# cc2652p_rf-star.net
KiCad netlist of a schematic drawn in EAGLE
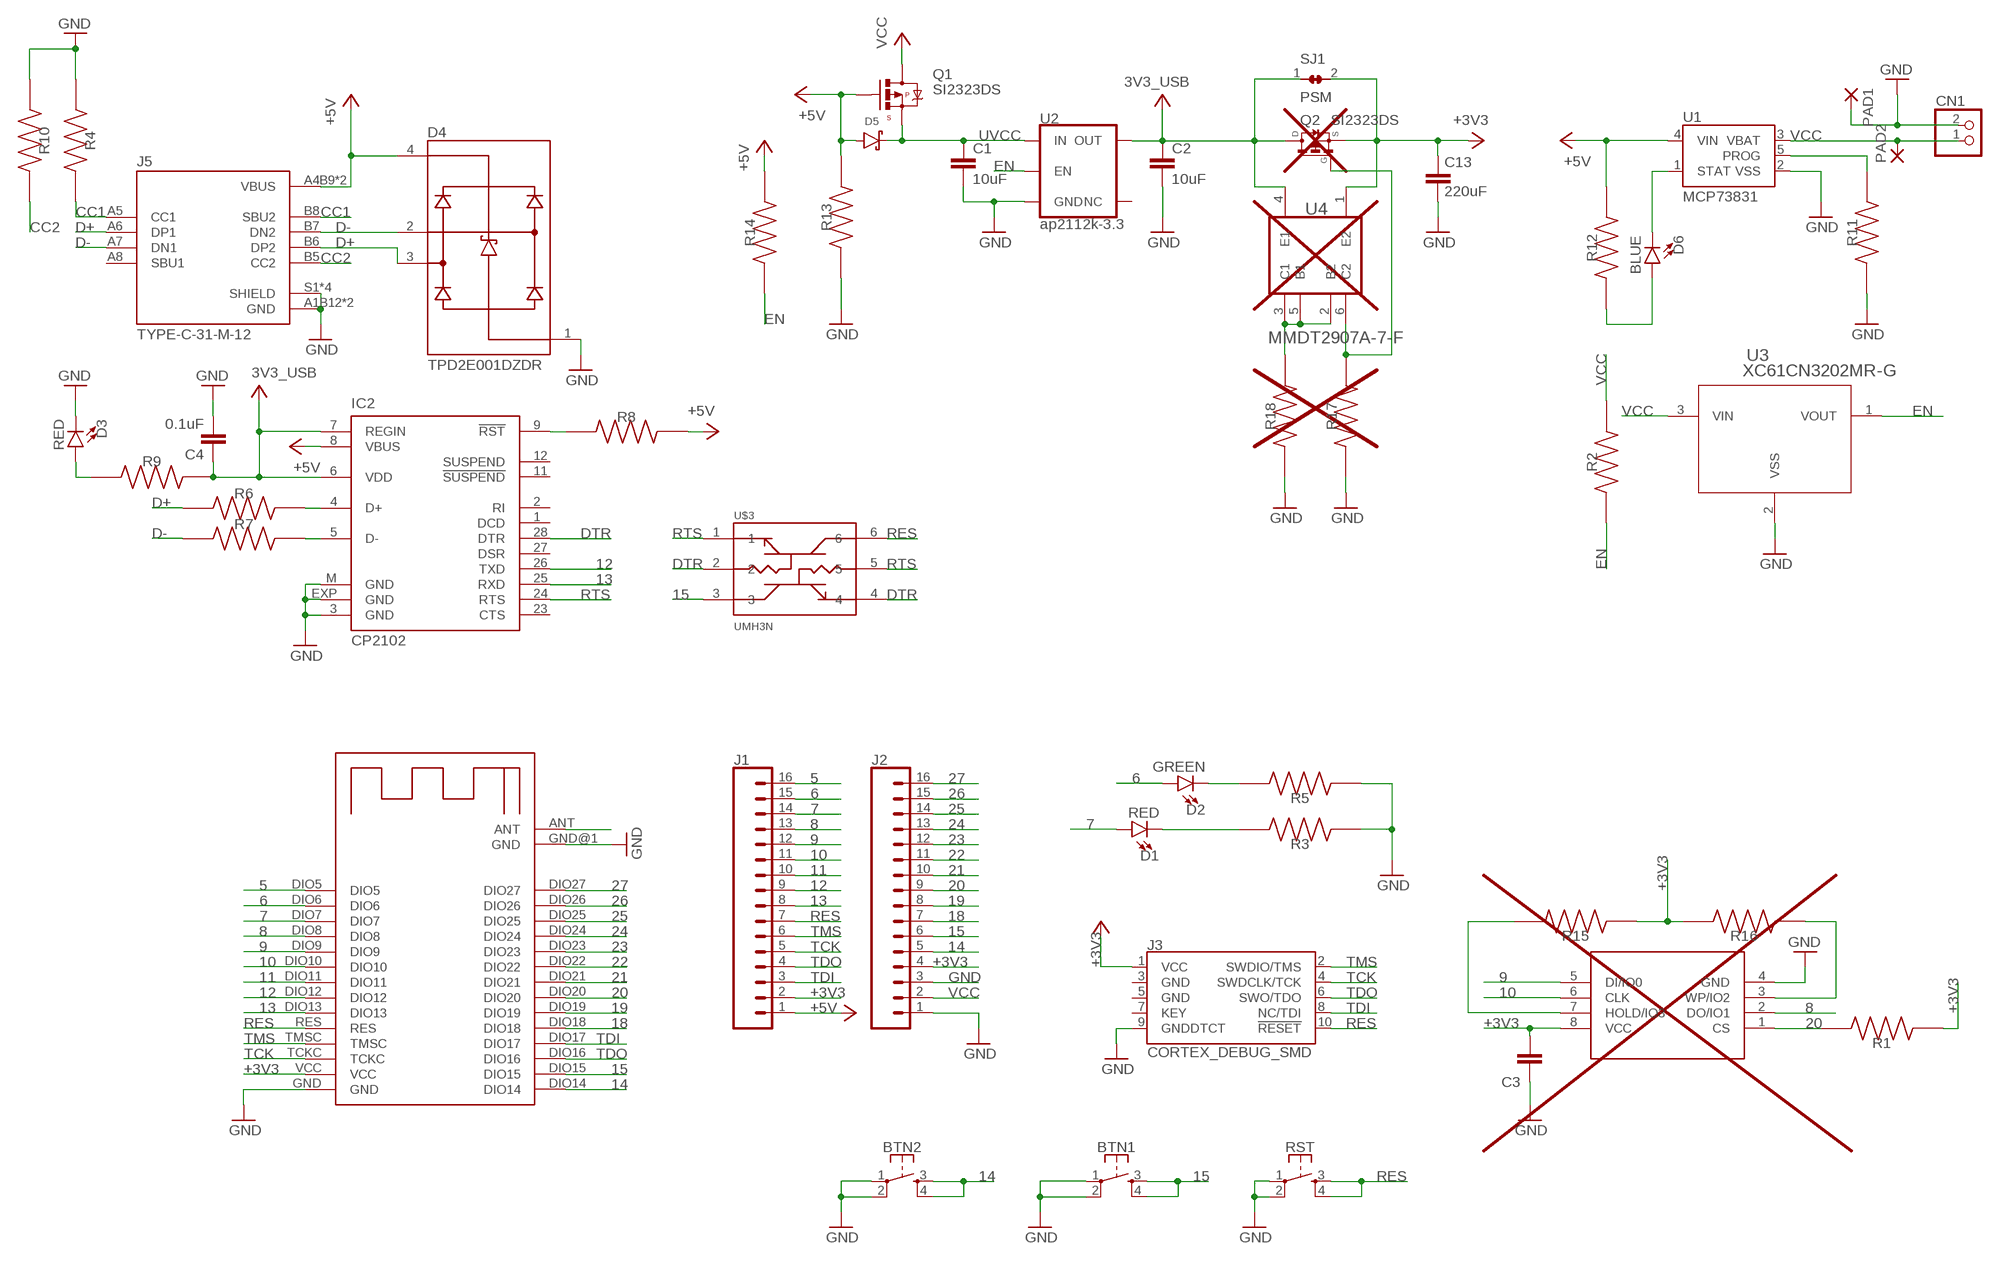
[diagram p0: schematic, sheet 1]

(export (version "E")
  (design (tool "Eeschema 10.0.6"))
  (components
    (comp (ref "BTN1")
      (value "MOMENTARY-SWITCH-SPST-2-SMD-4.6X2.8MM")
      (footprint "eagle-import:TACTILE_SWITCH_SMD_4.6X2.8MM")
      (libsource (lib "eagle-import") (part "MOMENTARY-SWITCH-SPST-2-SMD-4.6X2.8MM"))
    )
    (comp (ref "BTN2")
      (value "MOMENTARY-SWITCH-SPST-2-SMD-4.6X2.8MM")
      (footprint "eagle-import:TACTILE_SWITCH_SMD_4.6X2.8MM")
      (libsource (lib "eagle-import") (part "MOMENTARY-SWITCH-SPST-2-SMD-4.6X2.8MM"))
    )
    (comp (ref "C1")
      (value "10uF")
      (footprint "eagle-import:0603")
      (libsource (lib "eagle-import") (part "10UF-0603-6.3V-20%"))
    )
    (comp (ref "C2")
      (value "10uF")
      (footprint "eagle-import:0603")
      (libsource (lib "eagle-import") (part "10UF-0603-6.3V-20%"))
    )
    (comp (ref "C3")
      (value "100n")
      (footprint "eagle-import:CAPC1005X40N")
      (fields (field (name "MF") "Yageo") (field (name "MP") "RC0402FR-073M6L"))
      (libsource (lib "eagle-import") (part "CAP0402"))
    )
    (comp (ref "C4")
      (value "0.1uF")
      (footprint "eagle-import:0603")
      (libsource (lib "eagle-import") (part "0.1UF-0603-25V-(+80/-20%)"))
    )
    (comp (ref "C13")
      (value "220uF")
      (footprint "eagle-import:CAPM7343X310")
      (libsource (lib "eagle-import") (part "CTANTALUM-2917(7343-METRIC)_"))
    )
    (comp (ref "CN1")
      (value "JST_2PIN-SMT-RA")
      (footprint "eagle-import:JST-PH-2-SMT-RA")
      (libsource (lib "eagle-import") (part "JST_2PIN-SMT-RA"))
    )
    (comp (ref "D1")
      (value "RED")
      (footprint "eagle-import:LED-0603")
      (libsource (lib "eagle-import") (part "LED-RED0603"))
    )
    (comp (ref "D2")
      (value "GREEN")
      (footprint "eagle-import:LED-0603")
      (libsource (lib "eagle-import") (part "LED-GREEN0603"))
    )
    (comp (ref "D3")
      (value "RED")
      (footprint "eagle-import:LED-0603")
      (libsource (lib "eagle-import") (part "LED-RED0603"))
    )
    (comp (ref "D4")
      (value "TPD2E001DZDR")
      (footprint "eagle-import:SOT192P237X122-4N")
      (fields (field (name "MF") "Texas Instruments"))
      (libsource (lib "eagle-import") (part "TPD2E001DZDR"))
    )
    (comp (ref "D5")
      (value "DIODE-SCHOTTKY")
      (footprint "eagle-import:SOD-323")
      (libsource (lib "eagle-import") (part "DIODE-SCHOTTKY"))
    )
    (comp (ref "D6")
      (value "BLUE")
      (footprint "eagle-import:LED-0603")
      (libsource (lib "eagle-import") (part "LED-BLUE0603"))
    )
    (comp (ref "IC2")
      (value "CP2102")
      (footprint "eagle-import:MLP28")
      (fields (field (name "MF") "FARNELL") (field (name "MPN") "CP2102-GM"))
      (libsource (lib "eagle-import") (part "CP2102"))
    )
    (comp (ref "J1")
      (value "CONN_161X16_NO_SILK")
      (footprint "eagle-import:1X16_NO_SILK")
      (libsource (lib "eagle-import") (part "CONN_161X16_NO_SILK"))
    )
    (comp (ref "J2")
      (value "CONN_161X16_NO_SILK")
      (footprint "eagle-import:1X16_NO_SILK")
      (libsource (lib "eagle-import") (part "CONN_161X16_NO_SILK"))
    )
    (comp (ref "J3")
      (value "CORTEX_DEBUG_SMD")
      (footprint "eagle-import:SAMTECH_FTSH-105-01")
      (libsource (lib "eagle-import") (part "CORTEX_DEBUG_SMD"))
    )
    (comp (ref "J5")
      (value "TYPE-C-31-M-12")
      (footprint "eagle-import:HRO_TYPE-C-31-M-12")
      (fields (field (name "MF") "HRO Electronics Co., Ltd."))
      (libsource (lib "eagle-import") (part "TYPE-C-31-M-12"))
    )
    (comp (ref "PAD1")
      (value "WIREPADSMD1,27-254")
      (footprint "eagle-import:SMD1,27-2,54")
      (libsource (lib "eagle-import") (part "WIREPADSMD1,27-254"))
    )
    (comp (ref "PAD2")
      (value "WIREPADSMD1,27-254")
      (footprint "eagle-import:SMD1,27-2,54")
      (libsource (lib "eagle-import") (part "WIREPADSMD1,27-254"))
    )
    (comp (ref "Q1")
      (value "SI2323DS")
      (footprint "eagle-import:SOT23")
      (libsource (lib "eagle-import") (part "MOSFET-PCHANNEL"))
    )
    (comp (ref "Q2")
      (value "SI2323DS")
      (footprint "eagle-import:SOT23")
      (fields (field (name "MF") "Vishay Siliconix"))
      (libsource (lib "eagle-import") (part "SI2323DS"))
    )
    (comp (ref "R1")
      (value "2.2k")
      (footprint "eagle-import:RESC1005X40N")
      (fields (field (name "MF") "Yageo") (field (name "MP") "RC0402FR-073M6L"))
      (libsource (lib "eagle-import") (part "RC0402FR-073M6L"))
    )
    (comp (ref "R2")
      (value "10k")
      (footprint "eagle-import:RESC1005X40N")
      (fields (field (name "MF") "Yageo") (field (name "MP") "RC0402FR-073M6L"))
      (libsource (lib "eagle-import") (part "RC0402FR-073M6L"))
    )
    (comp (ref "R3")
      (value "2.2k")
      (footprint "eagle-import:RESC1005X40N")
      (fields (field (name "MF") "Yageo") (field (name "MP") "RC0402FR-073M6L"))
      (libsource (lib "eagle-import") (part "RC0402FR-073M6L"))
    )
    (comp (ref "R4")
      (value "5.1k")
      (footprint "eagle-import:RESC1005X40N")
      (fields (field (name "MF") "Yageo") (field (name "MP") "RC0402FR-073M6L"))
      (libsource (lib "eagle-import") (part "RC0402FR-073M6L"))
    )
    (comp (ref "R5")
      (value "2.2k")
      (footprint "eagle-import:RESC1005X40N")
      (fields (field (name "MF") "Yageo") (field (name "MP") "RC0402FR-073M6L"))
      (libsource (lib "eagle-import") (part "RC0402FR-073M6L"))
    )
    (comp (ref "R6")
      (value "33Ohm")
      (footprint "eagle-import:RESC1005X40N")
      (fields (field (name "MF") "Yageo") (field (name "MP") "RC0402FR-073M6L"))
      (libsource (lib "eagle-import") (part "RC0402FR-073M6L"))
    )
    (comp (ref "R7")
      (value "33Ohm")
      (footprint "eagle-import:RESC1005X40N")
      (fields (field (name "MF") "Yageo") (field (name "MP") "RC0402FR-073M6L"))
      (libsource (lib "eagle-import") (part "RC0402FR-073M6L"))
    )
    (comp (ref "R8")
      (value "4.7k")
      (footprint "eagle-import:RESC1005X40N")
      (fields (field (name "MF") "Yageo") (field (name "MP") "RC0402FR-073M6L"))
      (libsource (lib "eagle-import") (part "RC0402FR-073M6L"))
    )
    (comp (ref "R9")
      (value "2.2k")
      (footprint "eagle-import:RESC1005X40N")
      (fields (field (name "MF") "Yageo") (field (name "MP") "RC0402FR-073M6L"))
      (libsource (lib "eagle-import") (part "RC0402FR-073M6L"))
    )
    (comp (ref "R10")
      (value "5.1k")
      (footprint "eagle-import:RESC1005X40N")
      (fields (field (name "MF") "Yageo") (field (name "MP") "RC0402FR-073M6L"))
      (libsource (lib "eagle-import") (part "RC0402FR-073M6L"))
    )
    (comp (ref "R11")
      (value "2k")
      (footprint "eagle-import:RESC1005X40N")
      (fields (field (name "MF") "Yageo") (field (name "MP") "RC0402FR-073M6L"))
      (libsource (lib "eagle-import") (part "RC0402FR-073M6L"))
    )
    (comp (ref "R12")
      (value "2.2k")
      (footprint "eagle-import:RESC1005X40N")
      (fields (field (name "MF") "Yageo") (field (name "MP") "RC0402FR-073M6L"))
      (libsource (lib "eagle-import") (part "RC0402FR-073M6L"))
    )
    (comp (ref "R13")
      (value "100k")
      (footprint "eagle-import:RESC1005X40N")
      (fields (field (name "MF") "Yageo") (field (name "MP") "RC0402FR-073M6L"))
      (libsource (lib "eagle-import") (part "RC0402FR-073M6L"))
    )
    (comp (ref "R14")
      (value "10k")
      (footprint "eagle-import:RESC1005X40N")
      (fields (field (name "MF") "Yageo") (field (name "MP") "RC0402FR-073M6L"))
      (libsource (lib "eagle-import") (part "RC0402FR-073M6L"))
    )
    (comp (ref "R15")
      (value "0")
      (footprint "eagle-import:RESC1005X40N")
      (fields (field (name "MF") "Yageo") (field (name "MP") "RC0402FR-073M6L"))
      (libsource (lib "eagle-import") (part "RC0402FR-073M6L"))
    )
    (comp (ref "R16")
      (value "0")
      (footprint "eagle-import:RESC1005X40N")
      (fields (field (name "MF") "Yageo") (field (name "MP") "RC0402FR-073M6L"))
      (libsource (lib "eagle-import") (part "RC0402FR-073M6L"))
    )
    (comp (ref "R17")
      (value "100k")
      (footprint "eagle-import:RESC1005X40N")
      (fields (field (name "MF") "Yageo") (field (name "MP") "RC0402FR-073M6L"))
      (libsource (lib "eagle-import") (part "RC0402FR-073M6L"))
    )
    (comp (ref "R18")
      (value "100k")
      (footprint "eagle-import:RESC1005X40N")
      (fields (field (name "MF") "Yageo") (field (name "MP") "RC0402FR-073M6L"))
      (libsource (lib "eagle-import") (part "RC0402FR-073M6L"))
    )
    (comp (ref "RST")
      (value "MOMENTARY-SWITCH-SPST-2-SMD-4.6X2.8MM")
      (footprint "eagle-import:TACTILE_SWITCH_SMD_4.6X2.8MM")
      (libsource (lib "eagle-import") (part "MOMENTARY-SWITCH-SPST-2-SMD-4.6X2.8MM"))
    )
    (comp (ref "SJ1")
      (value "PSM")
      (footprint "eagle-import:SMALL_SOLDER_JUMPER_CLOSED")
      (libsource (lib "eagle-import") (part "SMALL_SOLDER_JUMPER_CLOSED"))
    )
    (comp (ref "U$1")
      (value "MX25R8035FM1IL0")
      (footprint "eagle-import:SO-8")
      (fields (field (name "MF") "Winbond Electronics") (field (name "MP") "W25Q80BVSNIG"))
      (libsource (lib "eagle-import") (part "W25Q80BVSNIG"))
    )
    (comp (ref "U$2")
      (value "RF-BM-2652P2")
      (footprint "eagle-import:RF-BM-2652P2")
      (libsource (lib "eagle-import") (part "RF-BM-2652P2"))
    )
    (comp (ref "U$3")
      (value "UMH3N")
      (footprint "eagle-import:SOP65P210X100-6N")
      (fields (field (name "MF") "Rohm"))
      (libsource (lib "eagle-import") (part "UMH3N"))
    )
    (comp (ref "U1")
      (value "MCP73831")
      (footprint "eagle-import:SOT23-5")
      (libsource (lib "eagle-import") (part "MCP73831"))
    )
    (comp (ref "U2")
      (value "ap2112k-3.3")
      (footprint "eagle-import:SOT23-5")
      (libsource (lib "eagle-import") (part "V_REG_AP2112K-3.3V"))
    )
    (comp (ref "U3")
      (value "XC61CN3202MR-G")
      (footprint "eagle-import:XC61C_SOT-23_TOR")
      (libsource (lib "eagle-import") (part "XC61CN3202MR-G"))
    )
    (comp (ref "U4")
      (value "MMDT2907A-7-F")
      (footprint "eagle-import:SOT65P210X110-6N")
      (fields (field (name "MF") "Diodes Inc."))
      (libsource (lib "eagle-import") (part "MMDT2907A-7-F"))
    )
  )
  (nets
    (net (code "1") (name "+3V3") (class "Default")
      (node (ref "C13") (pin "1") (pinfunction "1_1") (pintype "passive"))
      (node (ref "C3") (pin "2") (pinfunction "2_2") (pintype "passive"))
      (node (ref "J1") (pin "2") (pinfunction "2_2") (pintype "passive"))
      (node (ref "J2") (pin "4") (pinfunction "4_4") (pintype "passive"))
      (node (ref "J3") (pin "1") (pinfunction "VCC_1") (pintype "bidirectional"))
      (node (ref "Q2") (pin "2") (pinfunction "S_2") (pintype "passive"))
      (node (ref "R1") (pin "1") (pinfunction "1_1") (pintype "passive"))
      (node (ref "R15") (pin "1") (pinfunction "1_1") (pintype "passive"))
      (node (ref "R16") (pin "2") (pinfunction "2_2") (pintype "passive"))
      (node (ref "SJ1") (pin "2") (pinfunction "2_2") (pintype "bidirectional"))
      (node (ref "U$1") (pin "8") (pinfunction "VCC_8") (pintype "bidirectional"))
      (node (ref "U$2") (pin "VCC") (pinfunction "VCC_VCC") (pintype "bidirectional"))
      (node (ref "U4") (pin "1") (pinfunction "E2_1") (pintype "passive"))
    )
    (net (code "2") (name "+5V") (class "Default")
      (node (ref "D4") (pin "4") (pinfunction "VCC_4") (pintype "power_in"))
      (node (ref "D5") (pin "A") (pinfunction "A_A") (pintype "passive"))
      (node (ref "IC2") (pin "8") (pinfunction "VBUS_8") (pintype "input"))
      (node (ref "J1") (pin "1") (pinfunction "1_1") (pintype "passive"))
      (node (ref "J5") (pin "A4B9") (pinfunction "VBUS_A4B9") (pintype "power_in"))
      (node (ref "J5") (pin "B4A9") (pinfunction "VBUS_B4A9") (pintype "power_in"))
      (node (ref "Q1") (pin "1") (pinfunction "G_1") (pintype "passive"))
      (node (ref "R12") (pin "2") (pinfunction "2_2") (pintype "passive"))
      (node (ref "R13") (pin "2") (pinfunction "2_2") (pintype "passive"))
      (node (ref "R14") (pin "2") (pinfunction "2_2") (pintype "passive"))
      (node (ref "R8") (pin "2") (pinfunction "2_2") (pintype "passive"))
      (node (ref "U1") (pin "4") (pinfunction "VIN_4") (pintype "power_in"))
    )
    (net (code "3") (name "/5") (class "Default")
      (node (ref "J1") (pin "16") (pinfunction "16_16") (pintype "passive"))
      (node (ref "U$2") (pin "DIO5") (pinfunction "DIO5_DIO5") (pintype "bidirectional"))
    )
    (net (code "4") (name "/6") (class "Default")
      (node (ref "D2") (pin "A") (pinfunction "A_A") (pintype "passive"))
      (node (ref "J1") (pin "15") (pinfunction "15_15") (pintype "passive"))
      (node (ref "U$2") (pin "DIO6") (pinfunction "DIO6_DIO6") (pintype "bidirectional"))
    )
    (net (code "5") (name "/7") (class "Default")
      (node (ref "D1") (pin "A") (pinfunction "A_A") (pintype "passive"))
      (node (ref "J1") (pin "14") (pinfunction "14_14") (pintype "passive"))
      (node (ref "U$2") (pin "DIO7") (pinfunction "DIO7_DIO7") (pintype "bidirectional"))
    )
    (net (code "6") (name "/8") (class "Default")
      (node (ref "J1") (pin "13") (pinfunction "13_13") (pintype "passive"))
      (node (ref "U$1") (pin "2") (pinfunction "DO/IO1_2") (pintype "bidirectional"))
      (node (ref "U$2") (pin "DIO8") (pinfunction "DIO8_DIO8") (pintype "bidirectional"))
    )
    (net (code "7") (name "/9") (class "Default")
      (node (ref "J1") (pin "12") (pinfunction "12_12") (pintype "passive"))
      (node (ref "U$1") (pin "5") (pinfunction "DI/IO0_5") (pintype "bidirectional"))
      (node (ref "U$2") (pin "DIO9") (pinfunction "DIO9_DIO9") (pintype "bidirectional"))
    )
    (net (code "8") (name "/10") (class "Default")
      (node (ref "J1") (pin "11") (pinfunction "11_11") (pintype "passive"))
      (node (ref "U$1") (pin "6") (pinfunction "CLK_6") (pintype "bidirectional"))
      (node (ref "U$2") (pin "DIO10") (pinfunction "DIO10_DIO10") (pintype "bidirectional"))
    )
    (net (code "9") (name "/11") (class "Default")
      (node (ref "J1") (pin "10") (pinfunction "10_10") (pintype "passive"))
      (node (ref "U$2") (pin "DIO11") (pinfunction "DIO11_DIO11") (pintype "bidirectional"))
    )
    (net (code "10") (name "/12") (class "Default")
      (node (ref "IC2") (pin "26") (pinfunction "TXD_26") (pintype "output"))
      (node (ref "J1") (pin "9") (pinfunction "9_9") (pintype "passive"))
      (node (ref "U$2") (pin "DIO12") (pinfunction "DIO12_DIO12") (pintype "bidirectional"))
    )
    (net (code "11") (name "/13") (class "Default")
      (node (ref "IC2") (pin "25") (pinfunction "RXD_25") (pintype "input"))
      (node (ref "J1") (pin "8") (pinfunction "8_8") (pintype "passive"))
      (node (ref "U$2") (pin "DIO13") (pinfunction "DIO13_DIO13") (pintype "bidirectional"))
    )
    (net (code "12") (name "/14") (class "Default")
      (node (ref "BTN2") (pin "3") (pinfunction "3_3") (pintype "passive"))
      (node (ref "BTN2") (pin "4") (pinfunction "4_4") (pintype "passive"))
      (node (ref "J2") (pin "5") (pinfunction "5_5") (pintype "passive"))
      (node (ref "U$2") (pin "DIO14") (pinfunction "DIO14_DIO14") (pintype "bidirectional"))
    )
    (net (code "13") (name "/15") (class "Default")
      (node (ref "BTN1") (pin "3") (pinfunction "3_3") (pintype "passive"))
      (node (ref "BTN1") (pin "4") (pinfunction "4_4") (pintype "passive"))
      (node (ref "J2") (pin "6") (pinfunction "6_6") (pintype "passive"))
      (node (ref "U$2") (pin "DIO15") (pinfunction "DIO15_DIO15") (pintype "bidirectional"))
      (node (ref "U$3") (pin "3") (pinfunction "3_3") (pintype "bidirectional"))
    )
    (net (code "14") (name "/18") (class "Default")
      (node (ref "J2") (pin "7") (pinfunction "7_7") (pintype "passive"))
      (node (ref "U$2") (pin "DIO18") (pinfunction "DIO18_DIO18") (pintype "bidirectional"))
    )
    (net (code "15") (name "/19") (class "Default")
      (node (ref "J2") (pin "8") (pinfunction "8_8") (pintype "passive"))
      (node (ref "U$2") (pin "DIO19") (pinfunction "DIO19_DIO19") (pintype "bidirectional"))
    )
    (net (code "16") (name "/20") (class "Default")
      (node (ref "J2") (pin "9") (pinfunction "9_9") (pintype "passive"))
      (node (ref "R1") (pin "2") (pinfunction "2_2") (pintype "passive"))
      (node (ref "U$1") (pin "1") (pinfunction "CS_1") (pintype "bidirectional"))
      (node (ref "U$2") (pin "DIO20") (pinfunction "DIO20_DIO20") (pintype "bidirectional"))
    )
    (net (code "17") (name "/21") (class "Default")
      (node (ref "J2") (pin "10") (pinfunction "10_10") (pintype "passive"))
      (node (ref "U$2") (pin "DIO21") (pinfunction "DIO21_DIO21") (pintype "bidirectional"))
    )
    (net (code "18") (name "/22") (class "Default")
      (node (ref "J2") (pin "11") (pinfunction "11_11") (pintype "passive"))
      (node (ref "U$2") (pin "DIO22") (pinfunction "DIO22_DIO22") (pintype "bidirectional"))
    )
    (net (code "19") (name "/23") (class "Default")
      (node (ref "J2") (pin "12") (pinfunction "12_12") (pintype "passive"))
      (node (ref "U$2") (pin "DIO23") (pinfunction "DIO23_DIO23") (pintype "bidirectional"))
    )
    (net (code "20") (name "/24") (class "Default")
      (node (ref "J2") (pin "13") (pinfunction "13_13") (pintype "passive"))
      (node (ref "U$2") (pin "DIO24") (pinfunction "DIO24_DIO24") (pintype "bidirectional"))
    )
    (net (code "21") (name "/25") (class "Default")
      (node (ref "J2") (pin "14") (pinfunction "14_14") (pintype "passive"))
      (node (ref "U$2") (pin "DIO25") (pinfunction "DIO25_DIO25") (pintype "bidirectional"))
    )
    (net (code "22") (name "/26") (class "Default")
      (node (ref "J2") (pin "15") (pinfunction "15_15") (pintype "passive"))
      (node (ref "U$2") (pin "DIO26") (pinfunction "DIO26_DIO26") (pintype "bidirectional"))
    )
    (net (code "23") (name "/27") (class "Default")
      (node (ref "J2") (pin "16") (pinfunction "16_16") (pintype "passive"))
      (node (ref "U$2") (pin "DIO27") (pinfunction "DIO27_DIO27") (pintype "bidirectional"))
    )
    (net (code "24") (name "/CC1") (class "Default")
      (node (ref "J5") (pin "A5") (pinfunction "CC1_A5") (pintype "bidirectional"))
      (node (ref "J5") (pin "B8") (pinfunction "SBU2_B8") (pintype "bidirectional"))
      (node (ref "R4") (pin "2") (pinfunction "2_2") (pintype "passive"))
    )
    (net (code "25") (name "/CC2") (class "Default")
      (node (ref "J5") (pin "B5") (pinfunction "CC2_B5") (pintype "bidirectional"))
      (node (ref "R10") (pin "2") (pinfunction "2_2") (pintype "passive"))
    )
    (net (code "26") (name "/D+") (class "Default")
      (node (ref "D4") (pin "3") (pinfunction "IO2_3") (pintype "bidirectional"))
      (node (ref "J5") (pin "A6") (pinfunction "DP1_A6") (pintype "bidirectional"))
      (node (ref "J5") (pin "B6") (pinfunction "DP2_B6") (pintype "bidirectional"))
      (node (ref "R6") (pin "1") (pinfunction "1_1") (pintype "passive"))
    )
    (net (code "27") (name "/D-") (class "Default")
      (node (ref "D4") (pin "2") (pinfunction "IO1_2") (pintype "bidirectional"))
      (node (ref "J5") (pin "A7") (pinfunction "DN1_A7") (pintype "bidirectional"))
      (node (ref "J5") (pin "B7") (pinfunction "DN2_B7") (pintype "bidirectional"))
      (node (ref "R7") (pin "1") (pinfunction "1_1") (pintype "passive"))
    )
    (net (code "28") (name "/DTR") (class "Default")
      (node (ref "IC2") (pin "28") (pinfunction "DTR_28") (pintype "output"))
      (node (ref "U$3") (pin "2") (pinfunction "2_2") (pintype "bidirectional"))
      (node (ref "U$3") (pin "4") (pinfunction "4_4") (pintype "bidirectional"))
    )
    (net (code "29") (name "/EN") (class "Default")
      (node (ref "R14") (pin "1") (pinfunction "1_1") (pintype "passive"))
      (node (ref "R2") (pin "1") (pinfunction "1_1") (pintype "passive"))
      (node (ref "U2") (pin "3") (pinfunction "EN_3") (pintype "input"))
      (node (ref "U3") (pin "1") (pinfunction "VOUT_1") (pintype "output"))
    )
    (net (code "30") (name "/RES") (class "Default")
      (node (ref "J1") (pin "7") (pinfunction "7_7") (pintype "passive"))
      (node (ref "J3") (pin "10") (pinfunction "~{RESET}_10") (pintype "bidirectional"))
      (node (ref "RST") (pin "3") (pinfunction "3_3") (pintype "passive"))
      (node (ref "RST") (pin "4") (pinfunction "4_4") (pintype "passive"))
      (node (ref "U$2") (pin "RES") (pinfunction "RES_RES") (pintype "bidirectional"))
      (node (ref "U$3") (pin "6") (pinfunction "6_6") (pintype "bidirectional"))
    )
    (net (code "31") (name "/RTS") (class "Default")
      (node (ref "IC2") (pin "24") (pinfunction "RTS_24") (pintype "output"))
      (node (ref "U$3") (pin "1") (pinfunction "1_1") (pintype "bidirectional"))
      (node (ref "U$3") (pin "5") (pinfunction "5_5") (pintype "bidirectional"))
    )
    (net (code "32") (name "/TCK") (class "Default")
      (node (ref "J1") (pin "5") (pinfunction "5_5") (pintype "passive"))
      (node (ref "J3") (pin "4") (pinfunction "SWDCLK/TCK_4") (pintype "bidirectional"))
      (node (ref "U$2") (pin "TCKC") (pinfunction "TCKC_TCKC") (pintype "bidirectional"))
    )
    (net (code "33") (name "/TDI") (class "Default")
      (node (ref "J1") (pin "3") (pinfunction "3_3") (pintype "passive"))
      (node (ref "J3") (pin "8") (pinfunction "NC/TDI_8") (pintype "bidirectional"))
      (node (ref "U$2") (pin "DIO17") (pinfunction "DIO17_DIO17") (pintype "bidirectional"))
    )
    (net (code "34") (name "/TDO") (class "Default")
      (node (ref "J1") (pin "4") (pinfunction "4_4") (pintype "passive"))
      (node (ref "J3") (pin "6") (pinfunction "SWO/TDO_6") (pintype "bidirectional"))
      (node (ref "U$2") (pin "DIO16") (pinfunction "DIO16_DIO16") (pintype "bidirectional"))
    )
    (net (code "35") (name "/TMS") (class "Default")
      (node (ref "J1") (pin "6") (pinfunction "6_6") (pintype "passive"))
      (node (ref "J3") (pin "2") (pinfunction "SWDIO/TMS_2") (pintype "bidirectional"))
      (node (ref "U$2") (pin "TMSC") (pinfunction "TMSC_TMSC") (pintype "bidirectional"))
    )
    (net (code "36") (name "/UVCC") (class "Default")
      (node (ref "C1") (pin "1") (pinfunction "1_1") (pintype "passive"))
      (node (ref "D5") (pin "C") (pinfunction "C_C") (pintype "passive"))
      (node (ref "Q1") (pin "2") (pinfunction "S_2") (pintype "passive"))
      (node (ref "U2") (pin "1") (pinfunction "IN_1") (pintype "input"))
    )
    (net (code "37") (name "3V3_USB") (class "Default")
      (node (ref "C2") (pin "1") (pinfunction "1_1") (pintype "passive"))
      (node (ref "C4") (pin "1") (pinfunction "1_1") (pintype "passive"))
      (node (ref "IC2") (pin "6") (pinfunction "VDD_6") (pintype "power_in"))
      (node (ref "IC2") (pin "7") (pinfunction "REGIN_7") (pintype "passive"))
      (node (ref "Q2") (pin "3") (pinfunction "D_3") (pintype "passive"))
      (node (ref "R9") (pin "1") (pinfunction "1_1") (pintype "passive"))
      (node (ref "SJ1") (pin "1") (pinfunction "1_1") (pintype "bidirectional"))
      (node (ref "U2") (pin "5") (pinfunction "OUT_5") (pintype "passive"))
      (node (ref "U4") (pin "4") (pinfunction "E1_4") (pintype "passive"))
    )
    (net (code "38") (name "GND") (class "Default")
      (node (ref "BTN1") (pin "1") (pinfunction "1_1") (pintype "passive"))
      (node (ref "BTN1") (pin "2") (pinfunction "2_2") (pintype "passive"))
      (node (ref "BTN2") (pin "1") (pinfunction "1_1") (pintype "passive"))
      (node (ref "BTN2") (pin "2") (pinfunction "2_2") (pintype "passive"))
      (node (ref "C1") (pin "2") (pinfunction "2_2") (pintype "passive"))
      (node (ref "C13") (pin "2") (pinfunction "2_2") (pintype "passive"))
      (node (ref "C2") (pin "2") (pinfunction "2_2") (pintype "passive"))
      (node (ref "C3") (pin "1") (pinfunction "1_1") (pintype "passive"))
      (node (ref "C4") (pin "2") (pinfunction "2_2") (pintype "passive"))
      (node (ref "CN1") (pin "2") (pinfunction "1_2") (pintype "passive"))
      (node (ref "D3") (pin "C") (pinfunction "C_C") (pintype "passive"))
      (node (ref "D4") (pin "1") (pinfunction "GND_1") (pintype "power_in"))
      (node (ref "IC2") (pin "3") (pinfunction "GND_3") (pintype "power_in"))
      (node (ref "IC2") (pin "EXP") (pinfunction "GND_EXP") (pintype "power_in"))
      (node (ref "IC2") (pin "M") (pinfunction "GND_M") (pintype "power_in"))
      (node (ref "J2") (pin "1") (pinfunction "1_1") (pintype "passive"))
      (node (ref "J2") (pin "3") (pinfunction "3_3") (pintype "passive"))
      (node (ref "J3") (pin "9") (pinfunction "GNDDTCT_9") (pintype "bidirectional"))
      (node (ref "J5") (pin "A1B12") (pinfunction "GND_A1B12") (pintype "power_in"))
      (node (ref "J5") (pin "B1A12") (pinfunction "GND_B1A12") (pintype "power_in"))
      (node (ref "J5") (pin "S1") (pinfunction "SHIELD_S1") (pintype "passive"))
      (node (ref "J5") (pin "S2") (pinfunction "SHIELD_S2") (pintype "passive"))
      (node (ref "J5") (pin "S3") (pinfunction "SHIELD_S3") (pintype "passive"))
      (node (ref "J5") (pin "S4") (pinfunction "SHIELD_S4") (pintype "passive"))
      (node (ref "PAD1") (pin "1") (pinfunction "P_1") (pintype "passive"))
      (node (ref "R10") (pin "1") (pinfunction "1_1") (pintype "passive"))
      (node (ref "R11") (pin "1") (pinfunction "1_1") (pintype "passive"))
      (node (ref "R13") (pin "1") (pinfunction "1_1") (pintype "passive"))
      (node (ref "R17") (pin "1") (pinfunction "1_1") (pintype "passive"))
      (node (ref "R18") (pin "1") (pinfunction "1_1") (pintype "passive"))
      (node (ref "R3") (pin "1") (pinfunction "1_1") (pintype "passive"))
      (node (ref "R4") (pin "1") (pinfunction "1_1") (pintype "passive"))
      (node (ref "R5") (pin "1") (pinfunction "1_1") (pintype "passive"))
      (node (ref "RST") (pin "1") (pinfunction "1_1") (pintype "passive"))
      (node (ref "RST") (pin "2") (pinfunction "2_2") (pintype "passive"))
      (node (ref "U$1") (pin "4") (pinfunction "GND_4") (pintype "bidirectional"))
      (node (ref "U$2") (pin "GND") (pinfunction "GND_GND") (pintype "bidirectional"))
      (node (ref "U$2") (pin "GND@1") (pinfunction "GND_GND@1") (pintype "bidirectional"))
      (node (ref "U1") (pin "2") (pinfunction "VSS_2") (pintype "power_in"))
      (node (ref "U2") (pin "2") (pinfunction "GND_2") (pintype "input"))
      (node (ref "U3") (pin "2") (pinfunction "VSS_2") (pintype "passive"))
    )
    (net (code "39") (name "Net-(D1-PadC)") (class "Default")
      (node (ref "D1") (pin "C") (pinfunction "C_C") (pintype "passive"))
      (node (ref "R3") (pin "2") (pinfunction "2_2") (pintype "passive"))
    )
    (net (code "40") (name "Net-(D2-PadC)") (class "Default")
      (node (ref "D2") (pin "C") (pinfunction "C_C") (pintype "passive"))
      (node (ref "R5") (pin "2") (pinfunction "2_2") (pintype "passive"))
    )
    (net (code "41") (name "Net-(D3-PadA)") (class "Default")
      (node (ref "D3") (pin "A") (pinfunction "A_A") (pintype "passive"))
      (node (ref "R9") (pin "2") (pinfunction "2_2") (pintype "passive"))
    )
    (net (code "42") (name "Net-(D6-PadA)") (class "Default")
      (node (ref "D6") (pin "A") (pinfunction "A_A") (pintype "passive"))
      (node (ref "R12") (pin "1") (pinfunction "1_1") (pintype "passive"))
    )
    (net (code "43") (name "Net-(IC2-D+)") (class "Default")
      (node (ref "IC2") (pin "4") (pinfunction "D+_4") (pintype "bidirectional"))
      (node (ref "R6") (pin "2") (pinfunction "2_2") (pintype "passive"))
    )
    (net (code "44") (name "Net-(IC2-D-)") (class "Default")
      (node (ref "IC2") (pin "5") (pinfunction "D-_5") (pintype "bidirectional"))
      (node (ref "R7") (pin "2") (pinfunction "2_2") (pintype "passive"))
    )
    (net (code "45") (name "Net-(IC2-~{RST})") (class "Default")
      (node (ref "IC2") (pin "9") (pinfunction "~{RST}_9") (pintype "bidirectional"))
      (node (ref "R8") (pin "1") (pinfunction "1_1") (pintype "passive"))
    )
    (net (code "46") (name "Net-(Q2-G)") (class "Default")
      (node (ref "Q2") (pin "1") (pinfunction "G_1") (pintype "passive"))
      (node (ref "R17") (pin "2") (pinfunction "2_2") (pintype "passive"))
      (node (ref "U4") (pin "6") (pinfunction "C2_6") (pintype "passive"))
    )
    (net (code "47") (name "Net-(U$1-HOLD{slash}IO3)") (class "Default")
      (node (ref "R15") (pin "2") (pinfunction "2_2") (pintype "passive"))
      (node (ref "U$1") (pin "7") (pinfunction "HOLD/IO3_7") (pintype "bidirectional"))
    )
    (net (code "48") (name "Net-(U$1-WP{slash}IO2)") (class "Default")
      (node (ref "R16") (pin "1") (pinfunction "1_1") (pintype "passive"))
      (node (ref "U$1") (pin "3") (pinfunction "WP/IO2_3") (pintype "bidirectional"))
    )
    (net (code "49") (name "Net-(U1-PROG)") (class "Default")
      (node (ref "R11") (pin "2") (pinfunction "2_2") (pintype "passive"))
      (node (ref "U1") (pin "5") (pinfunction "PROG_5") (pintype "input"))
    )
    (net (code "50") (name "Net-(U1-STAT)") (class "Default")
      (node (ref "D6") (pin "C") (pinfunction "C_C") (pintype "passive"))
      (node (ref "U1") (pin "1") (pinfunction "STAT_1") (pintype "output"))
    )
    (net (code "51") (name "Net-(U4-B1)") (class "Default")
      (node (ref "R18") (pin "2") (pinfunction "2_2") (pintype "passive"))
      (node (ref "U4") (pin "2") (pinfunction "B2_2") (pintype "passive"))
      (node (ref "U4") (pin "3") (pinfunction "C1_3") (pintype "passive"))
      (node (ref "U4") (pin "5") (pinfunction "B1_5") (pintype "passive"))
    )
    (net (code "52") (name "VCC") (class "Default")
      (node (ref "CN1") (pin "1") (pinfunction "2_1") (pintype "passive"))
      (node (ref "J2") (pin "2") (pinfunction "2_2") (pintype "passive"))
      (node (ref "PAD2") (pin "1") (pinfunction "P_1") (pintype "passive"))
      (node (ref "Q1") (pin "3") (pinfunction "D_3") (pintype "passive"))
      (node (ref "R2") (pin "2") (pinfunction "2_2") (pintype "passive"))
      (node (ref "U1") (pin "3") (pinfunction "VBAT_3") (pintype "power_in"))
      (node (ref "U3") (pin "3") (pinfunction "VIN_3") (pintype "power_in"))
    )
    (net (code "53") (name "unconnected-(IC2-CTS-Pad23)") (class "Default")
      (node (ref "IC2") (pin "23") (pinfunction "CTS_23") (pintype "input"))
    )
    (net (code "54") (name "unconnected-(IC2-DCD-Pad1)") (class "Default")
      (node (ref "IC2") (pin "1") (pinfunction "DCD_1") (pintype "input"))
    )
    (net (code "55") (name "unconnected-(IC2-DSR-Pad27)") (class "Default")
      (node (ref "IC2") (pin "27") (pinfunction "DSR_27") (pintype "input"))
    )
    (net (code "56") (name "unconnected-(IC2-RI-Pad2)") (class "Default")
      (node (ref "IC2") (pin "2") (pinfunction "RI_2") (pintype "input"))
    )
    (net (code "57") (name "unconnected-(IC2-SUSPEND-Pad12)") (class "Default")
      (node (ref "IC2") (pin "12") (pinfunction "SUSPEND_12") (pintype "output"))
    )
    (net (code "58") (name "unconnected-(IC2-~{SUSPEND}-Pad11)") (class "Default")
      (node (ref "IC2") (pin "11") (pinfunction "~{SUSPEND}_11") (pintype "output"))
    )
    (net (code "59") (name "unconnected-(J3-GND-Pad3)") (class "Default")
      (node (ref "J3") (pin "3") (pinfunction "GND_3") (pintype "bidirectional"))
    )
    (net (code "60") (name "unconnected-(J3-GND-Pad5)") (class "Default")
      (node (ref "J3") (pin "5") (pinfunction "GND_5") (pintype "bidirectional"))
    )
    (net (code "61") (name "unconnected-(J3-KEY-Pad7)") (class "Default")
      (node (ref "J3") (pin "7") (pinfunction "KEY_7") (pintype "bidirectional"))
    )
    (net (code "62") (name "unconnected-(J5-SBU1-PadA8)") (class "Default")
      (node (ref "J5") (pin "A8") (pinfunction "SBU1_A8") (pintype "bidirectional"))
    )
    (net (code "63") (name "unconnected-(U$2-PadANT)") (class "Default")
      (node (ref "U$2") (pin "ANT") (pinfunction "ANT_ANT") (pintype "bidirectional"))
    )
    (net (code "64") (name "unconnected-(U2-NC-Pad4)") (class "Default")
      (node (ref "U2") (pin "4") (pinfunction "NC_4") (pintype "no_connect"))
    )
  )
)
